# SCH_NIRV2_Driver_2022-05-06.net
KiCad netlist of a schematic drawn in EasyEDA
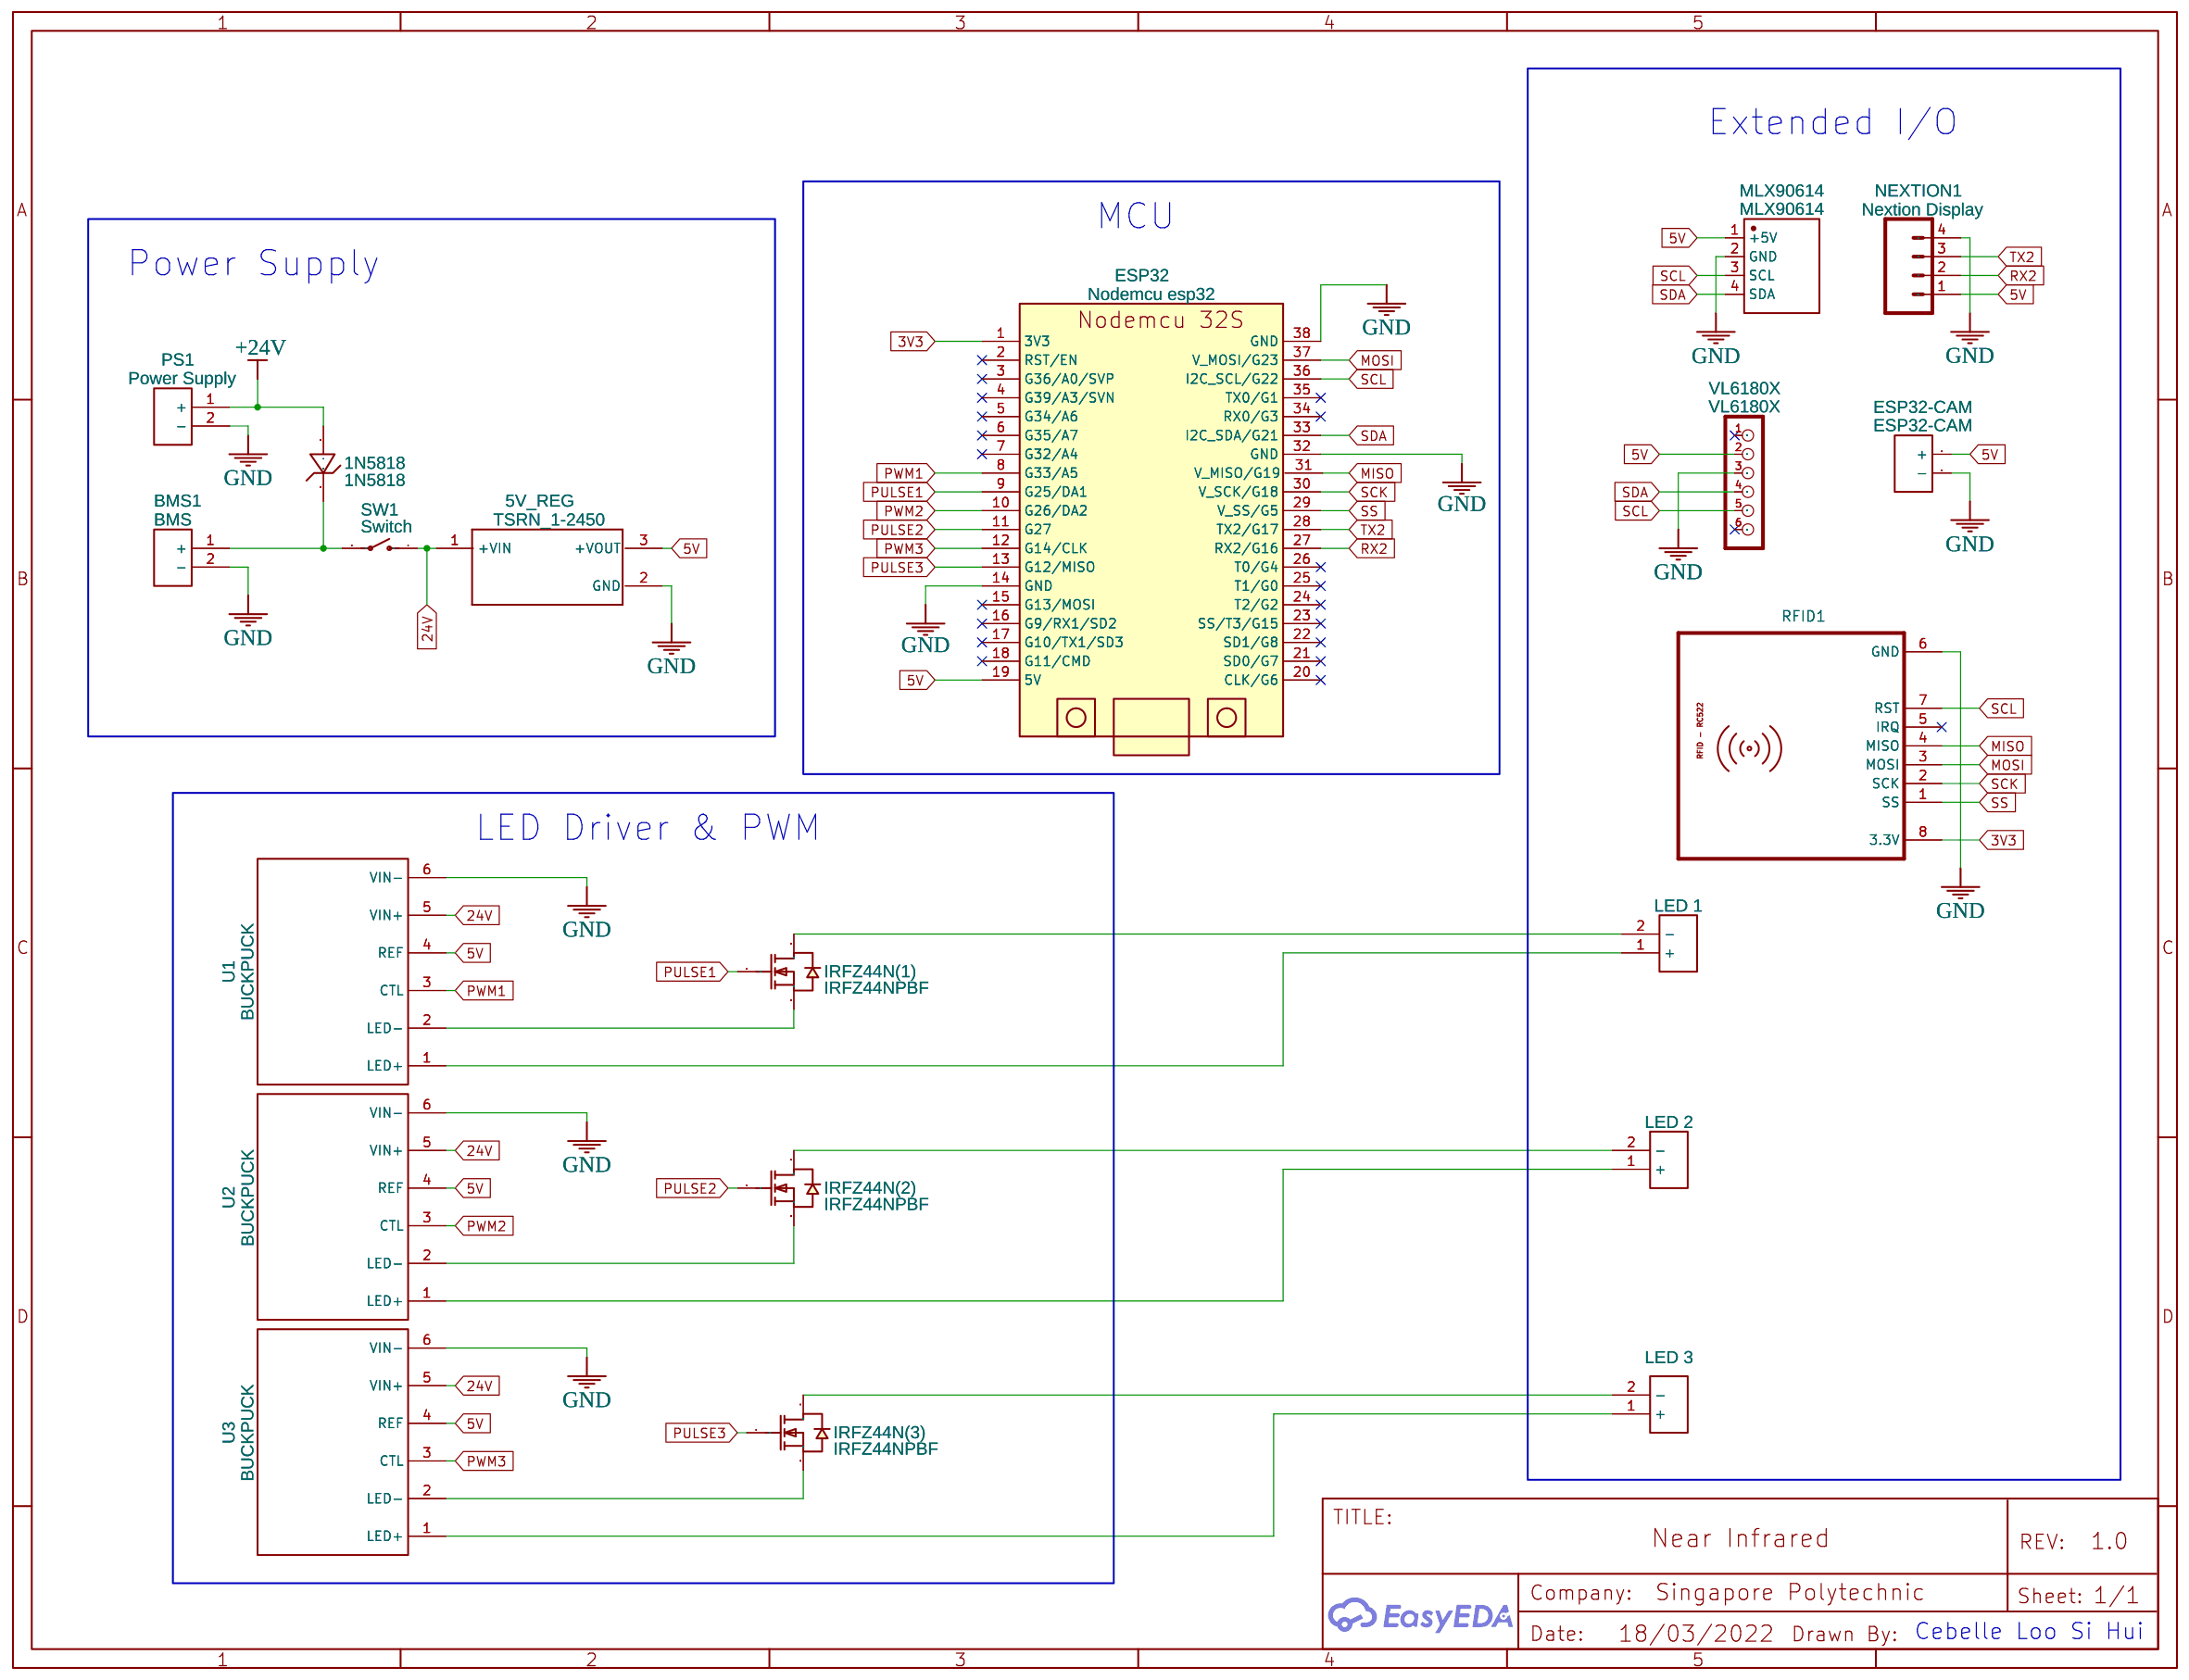
[diagram p0: schematic sheet]

(export (version "E")
  (design (tool "Eeschema 10.0.6"))
  (components
    (comp (ref "1N5818")
      (value "1N5818")
      (fields (field (name "BOM_Supplier Part") "C402217"))
      (libsource (lib "") (part "1N5818"))
    )
    (comp (ref "5V_REG") (value "TSRN_1-2450") (libsource (lib "") (part "TSRN_1-2450")))
    (comp (ref "BMS1")
      (value "BMS")
      (fields
        (field (name "BOM_Manufacturer Part") "WJ103-5.00-2P")
        (field (name "BOM_Supplier Part") "C8439")
      )
      (libsource (lib "") (part "WJ103-5.00-2P_2"))
    )
    (comp (ref "ESP32") (value "Nodemcu esp32") (libsource (lib "") (part "Nodemcu esp32")))
    (comp (ref "ESP32-CAM")
      (value "ESP32-CAM")
      (fields
        (field (name "BOM_Manufacturer Part") "2.54-1*2PFemale")
        (field (name "BOM_Supplier Part") "C49661")
      )
      (libsource (lib "") (part "Header-Female-2.54_1x2"))
    )
    (comp (ref "IRFZ44N(1)")
      (value "IRFZ44NPBF")
      (fields (field (name "BOM_Supplier Part") "C2586"))
      (libsource (lib "") (part "IRFZ44NPBF_1"))
    )
    (comp (ref "IRFZ44N(2)")
      (value "IRFZ44NPBF")
      (fields (field (name "BOM_Supplier Part") "C2586"))
      (libsource (lib "") (part "IRFZ44NPBF_2"))
    )
    (comp (ref "IRFZ44N(3)")
      (value "IRFZ44NPBF")
      (fields (field (name "BOM_Supplier Part") "C2586"))
      (libsource (lib "") (part "IRFZ44NPBF"))
    )
    (comp (ref "LED1")
      (value "LED 1")
      (fields
        (field (name "BOM_Manufacturer Part") "WJ103-5.00-2P")
        (field (name "BOM_Supplier Part") "C8439")
      )
      (libsource (lib "") (part "WJ103-5.00-2P"))
    )
    (comp (ref "LED2")
      (value "LED 2")
      (fields
        (field (name "BOM_Manufacturer Part") "WJ103-5.00-2P")
        (field (name "BOM_Supplier Part") "C8439")
      )
      (libsource (lib "") (part "WJ103-5.00-2P"))
    )
    (comp (ref "LED3")
      (value "LED 3")
      (fields
        (field (name "BOM_Manufacturer Part") "WJ103-5.00-2P")
        (field (name "BOM_Supplier Part") "C8439")
      )
      (libsource (lib "") (part "WJ103-5.00-2P"))
    )
    (comp (ref "MLX90614")
      (value "MLX90614")
      (fields
        (field (name "BOM_Manufacturer Part") "RE-H042TD-1190(LF)(SN)")
        (field (name "BOM_Supplier Part") "C265319")
      )
      (libsource (lib "") (part "RE-H042TD-1190(LF)(SN)"))
    )
    (comp (ref "NEXTION1") (value "Nextion Display") (libsource (lib "") (part "M04POLAR")))
    (comp (ref "PS1")
      (value "Power Supply")
      (fields
        (field (name "BOM_Manufacturer Part") "WJ103-5.00-2P")
        (field (name "BOM_Supplier Part") "C8439")
      )
      (libsource (lib "") (part "WJ103-5.00-2P_1"))
    )
    (comp (ref "RFID1") (value "NO") (libsource (lib "") (part "Unknown_954_-490")))
    (comp (ref "SW1")
      (value "Switch")
      (fields (field (name "BOM_Manufacturer Part") "KCD1-11-1.5x1cm"))
      (libsource (lib "") (part "SWITCH-2P-SPST-Rocker-10x15mm"))
    )
    (comp (ref "U1") (value "BUCKPUCK") (libsource (lib "") (part "BUCKPUCK")))
    (comp (ref "U2") (value "BUCKPUCK") (libsource (lib "") (part "BUCKPUCK")))
    (comp (ref "U3") (value "BUCKPUCK") (libsource (lib "") (part "BUCKPUCK")))
    (comp (ref "VL6180X") (value "VL6180X") (libsource (lib "") (part "CON_HEADER_1X06-PTH")))
  )
  (nets
    (net (code "1") (name "+24V") (class "Default")
      (node (ref "1N5818") (pin "2") (pinfunction "A_2") (pintype "unspecified"))
      (node (ref "PS1") (pin "1") (pinfunction "+_1") (pintype "unspecified"))
    )
    (net (code "2") (name "3V3") (class "Default")
      (node (ref "ESP32") (pin "1") (pinfunction "3V3_1") (pintype "passive"))
      (node (ref "RFID1") (pin "8") (pinfunction "3.3V_8") (pintype "unspecified"))
    )
    (net (code "3") (name "5V") (class "Default")
      (node (ref "5V_REG") (pin "3") (pinfunction "+VOUT_3") (pintype "bidirectional"))
      (node (ref "ESP32") (pin "19") (pinfunction "5V_19") (pintype "passive"))
      (node (ref "ESP32-CAM") (pin "2") (pinfunction "+_2") (pintype "input"))
      (node (ref "MLX90614") (pin "1") (pinfunction "+5V_1") (pintype "unspecified"))
      (node (ref "NEXTION1") (pin "1") (pinfunction "GND_1") (pintype "unspecified"))
      (node (ref "U1") (pin "4") (pinfunction "REF_4") (pintype "unspecified"))
      (node (ref "U2") (pin "4") (pinfunction "REF_4") (pintype "unspecified"))
      (node (ref "U3") (pin "4") (pinfunction "REF_4") (pintype "unspecified"))
      (node (ref "VL6180X") (pin "2") (pinfunction "VIN_2") (pintype "unspecified"))
    )
    (net (code "4") (name "24V") (class "Default")
      (node (ref "5V_REG") (pin "1") (pinfunction "+VIN_1") (pintype "bidirectional"))
      (node (ref "SW1") (pin "1") (pinfunction "O_1") (pintype "unspecified"))
      (node (ref "U1") (pin "5") (pinfunction "VIN+_5") (pintype "unspecified"))
      (node (ref "U2") (pin "5") (pinfunction "VIN+_5") (pintype "unspecified"))
      (node (ref "U3") (pin "5") (pinfunction "VIN+_5") (pintype "unspecified"))
    )
    (net (code "5") (name "GND") (class "Default")
      (node (ref "5V_REG") (pin "2") (pinfunction "GND_2") (pintype "bidirectional"))
      (node (ref "BMS1") (pin "2") (pinfunction "-_2") (pintype "unspecified"))
      (node (ref "ESP32") (pin "14") (pinfunction "GND_14") (pintype "passive"))
      (node (ref "ESP32") (pin "32") (pinfunction "GND_32") (pintype "passive"))
      (node (ref "ESP32") (pin "38") (pinfunction "GND_38") (pintype "passive"))
      (node (ref "ESP32-CAM") (pin "1") (pinfunction "-_1") (pintype "input"))
      (node (ref "MLX90614") (pin "2") (pinfunction "GND_2") (pintype "unspecified"))
      (node (ref "NEXTION1") (pin "4") (pinfunction "+5V_4") (pintype "unspecified"))
      (node (ref "PS1") (pin "2") (pinfunction "-_2") (pintype "unspecified"))
      (node (ref "RFID1") (pin "6") (pinfunction "GND_6") (pintype "unspecified"))
      (node (ref "U1") (pin "6") (pinfunction "VIN-_6") (pintype "unspecified"))
      (node (ref "U2") (pin "6") (pinfunction "VIN-_6") (pintype "unspecified"))
      (node (ref "U3") (pin "6") (pinfunction "VIN-_6") (pintype "unspecified"))
      (node (ref "VL6180X") (pin "3") (pinfunction "GND_3") (pintype "unspecified"))
    )
    (net (code "6") (name "MISO") (class "Default")
      (node (ref "ESP32") (pin "31") (pinfunction "V_MISO/G19_31") (pintype "bidirectional"))
      (node (ref "RFID1") (pin "4") (pinfunction "MISO_4") (pintype "unspecified"))
    )
    (net (code "7") (name "MOSI") (class "Default")
      (node (ref "ESP32") (pin "37") (pinfunction "V_MOSI/G23_37") (pintype "bidirectional"))
      (node (ref "RFID1") (pin "3") (pinfunction "MOSI_3") (pintype "unspecified"))
    )
    (net (code "8") (name "Net-(1N5818-C)") (class "Default")
      (node (ref "1N5818") (pin "1") (pinfunction "C_1") (pintype "unspecified"))
      (node (ref "BMS1") (pin "1") (pinfunction "+_1") (pintype "unspecified"))
      (node (ref "SW1") (pin "2") (pinfunction "P_2") (pintype "unspecified"))
    )
    (net (code "9") (name "Net-(IRFZ44N(1)-D)") (class "Default")
      (node (ref "IRFZ44N(1)") (pin "2") (pinfunction "D_2") (pintype "unspecified"))
      (node (ref "LED1") (pin "2") (pinfunction "-_2") (pintype "unspecified"))
    )
    (net (code "10") (name "Net-(IRFZ44N(1)-S)") (class "Default")
      (node (ref "IRFZ44N(1)") (pin "3") (pinfunction "S_3") (pintype "unspecified"))
      (node (ref "U1") (pin "2") (pinfunction "LED-_2") (pintype "unspecified"))
    )
    (net (code "11") (name "Net-(IRFZ44N(2)-D)") (class "Default")
      (node (ref "IRFZ44N(2)") (pin "2") (pinfunction "D_2") (pintype "unspecified"))
      (node (ref "LED2") (pin "2") (pinfunction "-_2") (pintype "unspecified"))
    )
    (net (code "12") (name "Net-(IRFZ44N(2)-S)") (class "Default")
      (node (ref "IRFZ44N(2)") (pin "3") (pinfunction "S_3") (pintype "unspecified"))
      (node (ref "U2") (pin "2") (pinfunction "LED-_2") (pintype "unspecified"))
    )
    (net (code "13") (name "Net-(IRFZ44N(3)-D)") (class "Default")
      (node (ref "IRFZ44N(3)") (pin "2") (pinfunction "D_2") (pintype "unspecified"))
      (node (ref "LED3") (pin "2") (pinfunction "-_2") (pintype "unspecified"))
    )
    (net (code "14") (name "Net-(IRFZ44N(3)-S)") (class "Default")
      (node (ref "IRFZ44N(3)") (pin "3") (pinfunction "S_3") (pintype "unspecified"))
      (node (ref "U3") (pin "2") (pinfunction "LED-_2") (pintype "unspecified"))
    )
    (net (code "15") (name "Net-(LED1-+)") (class "Default")
      (node (ref "LED1") (pin "1") (pinfunction "+_1") (pintype "unspecified"))
      (node (ref "U1") (pin "1") (pinfunction "LED+_1") (pintype "unspecified"))
    )
    (net (code "16") (name "Net-(LED2-+)") (class "Default")
      (node (ref "LED2") (pin "1") (pinfunction "+_1") (pintype "unspecified"))
      (node (ref "U2") (pin "1") (pinfunction "LED+_1") (pintype "unspecified"))
    )
    (net (code "17") (name "Net-(LED3-+)") (class "Default")
      (node (ref "LED3") (pin "1") (pinfunction "+_1") (pintype "unspecified"))
      (node (ref "U3") (pin "1") (pinfunction "LED+_1") (pintype "unspecified"))
    )
    (net (code "18") (name "PULSE1") (class "Default")
      (node (ref "ESP32") (pin "9") (pinfunction "G25/DA1_9") (pintype "bidirectional"))
      (node (ref "IRFZ44N(1)") (pin "1") (pinfunction "G_1") (pintype "unspecified"))
    )
    (net (code "19") (name "PULSE2") (class "Default")
      (node (ref "ESP32") (pin "11") (pinfunction "G27_11") (pintype "bidirectional"))
      (node (ref "IRFZ44N(2)") (pin "1") (pinfunction "G_1") (pintype "unspecified"))
    )
    (net (code "20") (name "PULSE3") (class "Default")
      (node (ref "ESP32") (pin "13") (pinfunction "G12/MISO_13") (pintype "bidirectional"))
      (node (ref "IRFZ44N(3)") (pin "1") (pinfunction "G_1") (pintype "unspecified"))
    )
    (net (code "21") (name "PWM1") (class "Default")
      (node (ref "ESP32") (pin "8") (pinfunction "G33/A5_8") (pintype "bidirectional"))
      (node (ref "U1") (pin "3") (pinfunction "CTL_3") (pintype "unspecified"))
    )
    (net (code "22") (name "PWM2") (class "Default")
      (node (ref "ESP32") (pin "10") (pinfunction "G26/DA2_10") (pintype "bidirectional"))
      (node (ref "U2") (pin "3") (pinfunction "CTL_3") (pintype "unspecified"))
    )
    (net (code "23") (name "PWM3") (class "Default")
      (node (ref "ESP32") (pin "12") (pinfunction "G14/CLK_12") (pintype "bidirectional"))
      (node (ref "U3") (pin "3") (pinfunction "CTL_3") (pintype "unspecified"))
    )
    (net (code "24") (name "RX2") (class "Default")
      (node (ref "ESP32") (pin "27") (pinfunction "RX2/G16_27") (pintype "bidirectional"))
      (node (ref "NEXTION1") (pin "2") (pinfunction "RX_2") (pintype "unspecified"))
    )
    (net (code "25") (name "SCK") (class "Default")
      (node (ref "ESP32") (pin "30") (pinfunction "V_SCK/G18_30") (pintype "bidirectional"))
      (node (ref "RFID1") (pin "2") (pinfunction "SCK_2") (pintype "unspecified"))
    )
    (net (code "26") (name "SCL") (class "Default")
      (node (ref "ESP32") (pin "36") (pinfunction "I2C_SCL/G22_36") (pintype "bidirectional"))
      (node (ref "MLX90614") (pin "3") (pinfunction "SCL_3") (pintype "unspecified"))
      (node (ref "RFID1") (pin "7") (pinfunction "RST_7") (pintype "unspecified"))
      (node (ref "VL6180X") (pin "5") (pinfunction "SCL_5") (pintype "unspecified"))
    )
    (net (code "27") (name "SDA") (class "Default")
      (node (ref "ESP32") (pin "33") (pinfunction "I2C_SDA/G21_33") (pintype "bidirectional"))
      (node (ref "MLX90614") (pin "4") (pinfunction "SDA_4") (pintype "unspecified"))
      (node (ref "VL6180X") (pin "4") (pinfunction "SDA_4") (pintype "unspecified"))
    )
    (net (code "28") (name "SS") (class "Default")
      (node (ref "ESP32") (pin "29") (pinfunction "V_SS/G5_29") (pintype "bidirectional"))
      (node (ref "RFID1") (pin "1") (pinfunction "SS_1") (pintype "unspecified"))
    )
    (net (code "29") (name "TX2") (class "Default")
      (node (ref "ESP32") (pin "28") (pinfunction "TX2/G17_28") (pintype "bidirectional"))
      (node (ref "NEXTION1") (pin "3") (pinfunction "TX_3") (pintype "unspecified"))
    )
    (net (code "30") (name "unconnected-(ESP32-CLK{slash}G6-Pad20)") (class "Default")
      (node (ref "ESP32") (pin "20") (pinfunction "CLK/G6_20") (pintype "bidirectional+no_connect"))
    )
    (net (code "31") (name "unconnected-(ESP32-G9{slash}RX1{slash}SD2-Pad16)") (class "Default")
      (node (ref "ESP32") (pin "16") (pinfunction "G9/RX1/SD2_16") (pintype "bidirectional+no_connect"))
    )
    (net (code "32") (name "unconnected-(ESP32-G10{slash}TX1{slash}SD3-Pad17)") (class "Default")
      (node (ref "ESP32") (pin "17") (pinfunction "G10/TX1/SD3_17") (pintype "bidirectional+no_connect"))
    )
    (net (code "33") (name "unconnected-(ESP32-G11{slash}CMD-Pad18)") (class "Default")
      (node (ref "ESP32") (pin "18") (pinfunction "G11/CMD_18") (pintype "bidirectional+no_connect"))
    )
    (net (code "34") (name "unconnected-(ESP32-G13{slash}MOSI-Pad15)") (class "Default")
      (node (ref "ESP32") (pin "15") (pinfunction "G13/MOSI_15") (pintype "bidirectional+no_connect"))
    )
    (net (code "35") (name "unconnected-(ESP32-G32{slash}A4-Pad7)") (class "Default")
      (node (ref "ESP32") (pin "7") (pinfunction "G32/A4_7") (pintype "bidirectional+no_connect"))
    )
    (net (code "36") (name "unconnected-(ESP32-G34{slash}A6-Pad5)") (class "Default")
      (node (ref "ESP32") (pin "5") (pinfunction "G34/A6_5") (pintype "bidirectional+no_connect"))
    )
    (net (code "37") (name "unconnected-(ESP32-G35{slash}A7-Pad6)") (class "Default")
      (node (ref "ESP32") (pin "6") (pinfunction "G35/A7_6") (pintype "bidirectional+no_connect"))
    )
    (net (code "38") (name "unconnected-(ESP32-G36{slash}A0{slash}SVP-Pad3)") (class "Default")
      (node (ref "ESP32") (pin "3") (pinfunction "G36/A0/SVP_3") (pintype "bidirectional+no_connect"))
    )
    (net (code "39") (name "unconnected-(ESP32-G39{slash}A3{slash}SVN-Pad4)") (class "Default")
      (node (ref "ESP32") (pin "4") (pinfunction "G39/A3/SVN_4") (pintype "bidirectional+no_connect"))
    )
    (net (code "40") (name "unconnected-(ESP32-RST{slash}EN-Pad2)") (class "Default")
      (node (ref "ESP32") (pin "2") (pinfunction "RST/EN_2") (pintype "bidirectional+no_connect"))
    )
    (net (code "41") (name "unconnected-(ESP32-RX0{slash}G3-Pad34)") (class "Default")
      (node (ref "ESP32") (pin "34") (pinfunction "RX0/G3_34") (pintype "bidirectional+no_connect"))
    )
    (net (code "42") (name "unconnected-(ESP32-SD0{slash}G7-Pad21)") (class "Default")
      (node (ref "ESP32") (pin "21") (pinfunction "SD0/G7_21") (pintype "bidirectional+no_connect"))
    )
    (net (code "43") (name "unconnected-(ESP32-SD1{slash}G8-Pad22)") (class "Default")
      (node (ref "ESP32") (pin "22") (pinfunction "SD1/G8_22") (pintype "bidirectional+no_connect"))
    )
    (net (code "44") (name "unconnected-(ESP32-SS{slash}T3{slash}G15-Pad23)") (class "Default")
      (node (ref "ESP32") (pin "23") (pinfunction "SS/T3/G15_23") (pintype "bidirectional+no_connect"))
    )
    (net (code "45") (name "unconnected-(ESP32-T0{slash}G4-Pad26)") (class "Default")
      (node (ref "ESP32") (pin "26") (pinfunction "T0/G4_26") (pintype "bidirectional+no_connect"))
    )
    (net (code "46") (name "unconnected-(ESP32-T1{slash}G0-Pad25)") (class "Default")
      (node (ref "ESP32") (pin "25") (pinfunction "T1/G0_25") (pintype "bidirectional+no_connect"))
    )
    (net (code "47") (name "unconnected-(ESP32-T2{slash}G2-Pad24)") (class "Default")
      (node (ref "ESP32") (pin "24") (pinfunction "T2/G2_24") (pintype "bidirectional+no_connect"))
    )
    (net (code "48") (name "unconnected-(ESP32-TX0{slash}G1-Pad35)") (class "Default")
      (node (ref "ESP32") (pin "35") (pinfunction "TX0/G1_35") (pintype "bidirectional+no_connect"))
    )
    (net (code "49") (name "unconnected-(RFID1-IRQ-Pad5)") (class "Default")
      (node (ref "RFID1") (pin "5") (pinfunction "IRQ_5") (pintype "unspecified+no_connect"))
    )
    (net (code "50") (name "unconnected-(VL6180X-IO1-Pad6)") (class "Default")
      (node (ref "VL6180X") (pin "6") (pinfunction "IO1_6") (pintype "unspecified+no_connect"))
    )
    (net (code "51") (name "unconnected-(VL6180X-VDD-Pad1)") (class "Default")
      (node (ref "VL6180X") (pin "1") (pinfunction "VDD_1") (pintype "unspecified+no_connect"))
    )
  )
)
